# RAVEN_1_0.net
KiCad netlist of a schematic drawn in Altium Designer
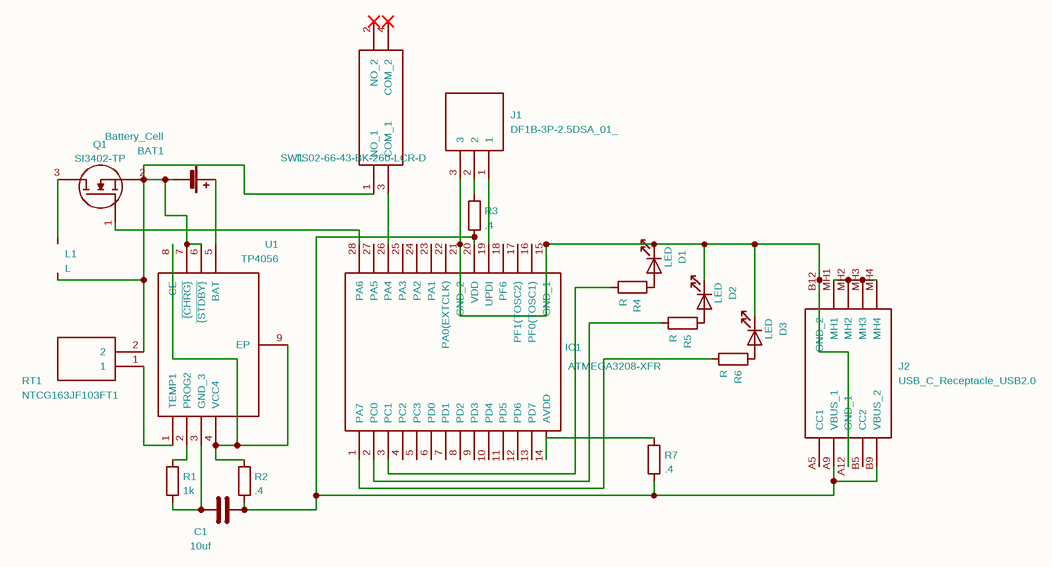
[diagram p0: RAVEN 1.0.SchDoc]

(export (version "E")
  (design (tool "Eeschema 10.0.6"))
  (components
    (comp (ref "BAT1") (value "Battery_Cell") (libsource (lib "Device") (part "Battery_Cell")))
    (comp (ref "C1") (value "10uf") (libsource (lib "Device") (part "C")))
    (comp (ref "D1") (value "LED") (libsource (lib "Device") (part "LED")))
    (comp (ref "D2") (value "LED") (libsource (lib "Device") (part "LED")))
    (comp (ref "D3") (value "LED") (libsource (lib "Device") (part "LED")))
    (comp (ref "IC1")
      (value "ATMEGA3208-XFR")
      (description "8-bit Microcontrollers - MCU 20MHz, 32KB, SSOP28, Ind 125C, Green, T&R")
      (fields (field (name "MOUSER PART NUMBER") "556-ATMEGA3208-XFR"))
      (libsource (lib "SamacSys_Parts_OLD") (part "ATMEGA3208-XFR"))
    )
    (comp (ref "J1")
      (value "DF1B-3P-2.5DSA_01_")
      (description "Headers & Wire Housings 2.5MM V SNG ROW HDR 3P THRU-HOLE GOLD")
      (fields
        (field (name "MANUFACTURER_PART_NUMBER") "DF1B-3P-2.5DSA(01)")
        (field (name "MOUSER PART NUMBER") "798-DF1B-3P-2.5DSA01")
      )
      (libsource (lib "SamacSys_Parts") (part "DF1B-3P-2.5DSA_01_"))
    )
    (comp (ref "J2")
      (value "USB_C_Receptacle_USB2.0")
      (description "USB Connectors USB C Rec GF RA 6P SMT TH Stakes 1.9mm")
      (fields
        (field (name "MANUFACTURER_PART_NUMBER") "USB4125-GF-A-0190")
        (field (name "MOUSER PART NUMBER") "640-USB4125-GF-A-190")
      )
      (libsource (lib "SamacSys_Parts") (part "USB4125-GF-A-0190"))
    )
    (comp (ref "L1") (value "L") (libsource (lib "Device") (part "L")))
    (comp (ref "Q1")
      (value "SI3402-TP")
      (description "MOSFET 30V,4A,N-CHANNEL MOSFET,SOT-23")
      (fields (field (name "MOUSER PART NUMBER") "833-SI3402-TP"))
      (libsource (lib "SamacSys_Parts_OLD") (part "SI3402-TP"))
    )
    (comp (ref "R1") (value "1k") (libsource (lib "") (part "R_1")))
    (comp (ref "R2") (value ".4") (libsource (lib "") (part "R_1")))
    (comp (ref "R3") (value ".4") (libsource (lib "") (part "R_1")))
    (comp (ref "R4") (value "R") (libsource (lib "Device") (part "R")))
    (comp (ref "R5") (value "R") (libsource (lib "Device") (part "R")))
    (comp (ref "R6") (value "R") (libsource (lib "Device") (part "R")))
    (comp (ref "R7") (value ".4") (libsource (lib "") (part "R_1")))
    (comp (ref "RT1")
      (value "NTCG163JF103FT1")
      (description "Chip NTC Thermistors (Sensor), Resistance (at 25?C)=10k?, Resistance Tolerance (at 25?C)=?1%")
      (fields (field (name "MOUSER PART NUMBER") "810-NTCG163JF103FT1"))
      (libsource (lib "SamacSys_Parts_OLD") (part "NTCG163JF103FT1"))
    )
    (comp (ref "SW1")
      (value "TS02-66-43-BK-260-LCR-D")
      (description "Tactile Switches 6 x 6 mm, 4.3 mm Act Height, 260 gf, Black, Long Crimped, Through Hole, SPST,")
      (fields (field (name "MOUSER PART NUMBER") "179-TS026643BK260LCR"))
      (libsource (lib "SamacSys_Parts") (part "TS02-66-43-BK-260-LCR-D"))
    )
    (comp (ref "U1")
      (value "TP4056")
      (description "1A Standalone Linear Li-lon Battery Charger, SOP-8")
      (libsource (lib "SamacSys_Parts_OLD") (part "TP4056"))
    )
  )
  (nets
    (net (code "1") (name "Net-(BAT1-+)") (class "Default")
      (node (ref "BAT1") (pin "1") (pinfunction "+_1") (pintype "passive"))
      (node (ref "U1") (pin "5") (pinfunction "BAT_5") (pintype "passive"))
    )
    (net (code "2") (name "Net-(BAT1--)") (class "Default")
      (node (ref "BAT1") (pin "2") (pinfunction "-_2") (pintype "passive"))
      (node (ref "L1") (pin "2") (pinfunction "2_2") (pintype "passive"))
      (node (ref "Q1") (pin "2") (pinfunction "2_2") (pintype "passive"))
      (node (ref "RT1") (pin "2") (pinfunction "2_2") (pintype "passive"))
      (node (ref "SW1") (pin "1") (pinfunction "NO_1_1") (pintype "passive"))
      (node (ref "U1") (pin "6") (pinfunction "~{{STDBY}}_6") (pintype "passive"))
      (node (ref "U1") (pin "7") (pinfunction "~{{CHRG}}_7") (pintype "passive"))
    )
    (net (code "3") (name "Net-(D1-A)") (class "Default")
      (node (ref "D1") (pin "2") (pinfunction "A_2") (pintype "passive"))
      (node (ref "R4") (pin "1") (pinfunction "1_1") (pintype "passive"))
    )
    (net (code "4") (name "Net-(D1-K)") (class "Default")
      (node (ref "D1") (pin "1") (pinfunction "K_1") (pintype "passive"))
      (node (ref "D2") (pin "1") (pinfunction "K_1") (pintype "passive"))
      (node (ref "D3") (pin "1") (pinfunction "K_1") (pintype "passive"))
      (node (ref "IC1") (pin "15") (pinfunction "GND_1_15") (pintype "passive"))
      (node (ref "IC1") (pin "21") (pinfunction "GND_2_21") (pintype "passive"))
      (node (ref "J1") (pin "3") (pinfunction "3_3") (pintype "passive"))
      (node (ref "J2") (pin "A12") (pinfunction "GND_1_A12") (pintype "passive"))
      (node (ref "J2") (pin "B12") (pinfunction "GND_2_B12") (pintype "passive"))
    )
    (net (code "5") (name "Net-(D2-A)") (class "Default")
      (node (ref "D2") (pin "2") (pinfunction "A_2") (pintype "passive"))
      (node (ref "R5") (pin "1") (pinfunction "1_1") (pintype "passive"))
    )
    (net (code "6") (name "Net-(D3-A)") (class "Default")
      (node (ref "D3") (pin "2") (pinfunction "A_2") (pintype "passive"))
      (node (ref "R6") (pin "1") (pinfunction "1_1") (pintype "passive"))
    )
    (net (code "7") (name "Net-(IC1-AVDD)") (class "Default")
      (node (ref "IC1") (pin "14") (pinfunction "AVDD_14") (pintype "passive"))
      (node (ref "R7") (pin "1") (pinfunction "1_1") (pintype "passive"))
    )
    (net (code "8") (name "Net-(IC1-PA4)") (class "Default")
      (node (ref "IC1") (pin "26") (pinfunction "PA4_26") (pintype "passive"))
      (node (ref "SW1") (pin "3") (pinfunction "COM_1_3") (pintype "passive"))
    )
    (net (code "9") (name "Net-(IC1-PA6)") (class "Default")
      (node (ref "IC1") (pin "28") (pinfunction "PA6_28") (pintype "passive"))
      (node (ref "Q1") (pin "1") (pinfunction "1_1") (pintype "passive"))
    )
    (net (code "10") (name "Net-(IC1-PA7)") (class "Default")
      (node (ref "IC1") (pin "1") (pinfunction "PA7_1") (pintype "passive"))
      (node (ref "R6") (pin "2") (pinfunction "2_2") (pintype "passive"))
    )
    (net (code "11") (name "Net-(IC1-PC0)") (class "Default")
      (node (ref "IC1") (pin "2") (pinfunction "PC0_2") (pintype "passive"))
      (node (ref "R5") (pin "2") (pinfunction "2_2") (pintype "passive"))
    )
    (net (code "12") (name "Net-(IC1-PC1)") (class "Default")
      (node (ref "IC1") (pin "3") (pinfunction "PC1_3") (pintype "passive"))
      (node (ref "R4") (pin "2") (pinfunction "2_2") (pintype "passive"))
    )
    (net (code "13") (name "Net-(IC1-UPDI)") (class "Default")
      (node (ref "IC1") (pin "19") (pinfunction "UPDI_19") (pintype "passive"))
      (node (ref "J1") (pin "1") (pinfunction "1_1") (pintype "passive"))
    )
    (net (code "14") (name "Net-(IC1-VDD)") (class "Default")
      (node (ref "C1") (pin "2") (pinfunction "2_2") (pintype "passive"))
      (node (ref "IC1") (pin "20") (pinfunction "VDD_20") (pintype "passive"))
      (node (ref "J2") (pin "A9") (pinfunction "VBUS_1_A9") (pintype "passive"))
      (node (ref "J2") (pin "B9") (pinfunction "VBUS_2_B9") (pintype "passive"))
      (node (ref "R2") (pin "2") (pinfunction "2_2") (pintype "passive"))
      (node (ref "R3") (pin "2") (pinfunction "2_2") (pintype "passive"))
      (node (ref "R7") (pin "2") (pinfunction "2_2") (pintype "passive"))
    )
    (net (code "15") (name "Net-(J1-Pad2)") (class "Default")
      (node (ref "J1") (pin "2") (pinfunction "2_2") (pintype "passive"))
      (node (ref "R3") (pin "1") (pinfunction "1_1") (pintype "passive"))
    )
    (net (code "16") (name "Net-(J2-PadMH1)") (class "Default")
      (node (ref "J2") (pin "MH1") (pinfunction "MH1_MH1") (pintype "passive"))
      (node (ref "J2") (pin "MH2") (pinfunction "MH2_MH2") (pintype "passive"))
      (node (ref "J2") (pin "MH3") (pinfunction "MH3_MH3") (pintype "passive"))
      (node (ref "J2") (pin "MH4") (pinfunction "MH4_MH4") (pintype "passive"))
    )
    (net (code "17") (name "Net-(L1-Pad1)") (class "Default")
      (node (ref "L1") (pin "1") (pinfunction "1_1") (pintype "passive"))
      (node (ref "Q1") (pin "3") (pinfunction "3_3") (pintype "passive"))
    )
    (net (code "18") (name "Net-(U1-CE)") (class "Default")
      (node (ref "R2") (pin "1") (pinfunction "1_1") (pintype "passive"))
      (node (ref "U1") (pin "4") (pinfunction "VCC4_4") (pintype "passive"))
      (node (ref "U1") (pin "8") (pinfunction "CE_8") (pintype "passive"))
      (node (ref "U1") (pin "9") (pinfunction "EP_9") (pintype "passive"))
    )
    (net (code "19") (name "Net-(U1-GND_3)") (class "Default")
      (node (ref "C1") (pin "1") (pinfunction "1_1") (pintype "passive"))
      (node (ref "R1") (pin "2") (pinfunction "2_2") (pintype "passive"))
      (node (ref "U1") (pin "3") (pinfunction "GND_3_3") (pintype "passive"))
    )
    (net (code "20") (name "Net-(U1-PROG2)") (class "Default")
      (node (ref "R1") (pin "1") (pinfunction "1_1") (pintype "passive"))
      (node (ref "U1") (pin "2") (pinfunction "PROG2_2") (pintype "passive"))
    )
    (net (code "21") (name "Net-(U1-TEMP1)") (class "Default")
      (node (ref "RT1") (pin "1") (pinfunction "1_1") (pintype "passive"))
      (node (ref "U1") (pin "1") (pinfunction "TEMP1_1") (pintype "passive"))
    )
    (net (code "22") (name "unconnected-(IC1-PA0(EXTCLK)-Pad22)") (class "Default")
      (node (ref "IC1") (pin "22") (pinfunction "PA0(EXTCLK)_22") (pintype "passive"))
    )
    (net (code "23") (name "unconnected-(IC1-PA1-Pad23)") (class "Default")
      (node (ref "IC1") (pin "23") (pinfunction "PA1_23") (pintype "passive"))
    )
    (net (code "24") (name "unconnected-(IC1-PA2-Pad24)") (class "Default")
      (node (ref "IC1") (pin "24") (pinfunction "PA2_24") (pintype "passive"))
    )
    (net (code "25") (name "unconnected-(IC1-PA3-Pad25)") (class "Default")
      (node (ref "IC1") (pin "25") (pinfunction "PA3_25") (pintype "passive"))
    )
    (net (code "26") (name "unconnected-(IC1-PA5-Pad27)") (class "Default")
      (node (ref "IC1") (pin "27") (pinfunction "PA5_27") (pintype "passive"))
    )
    (net (code "27") (name "unconnected-(IC1-PC2-Pad4)") (class "Default")
      (node (ref "IC1") (pin "4") (pinfunction "PC2_4") (pintype "passive"))
    )
    (net (code "28") (name "unconnected-(IC1-PC3-Pad5)") (class "Default")
      (node (ref "IC1") (pin "5") (pinfunction "PC3_5") (pintype "passive"))
    )
    (net (code "29") (name "unconnected-(IC1-PD0-Pad6)") (class "Default")
      (node (ref "IC1") (pin "6") (pinfunction "PD0_6") (pintype "passive"))
    )
    (net (code "30") (name "unconnected-(IC1-PD1-Pad7)") (class "Default")
      (node (ref "IC1") (pin "7") (pinfunction "PD1_7") (pintype "passive"))
    )
    (net (code "31") (name "unconnected-(IC1-PD2-Pad8)") (class "Default")
      (node (ref "IC1") (pin "8") (pinfunction "PD2_8") (pintype "passive"))
    )
    (net (code "32") (name "unconnected-(IC1-PD3-Pad9)") (class "Default")
      (node (ref "IC1") (pin "9") (pinfunction "PD3_9") (pintype "passive"))
    )
    (net (code "33") (name "unconnected-(IC1-PD4-Pad10)") (class "Default")
      (node (ref "IC1") (pin "10") (pinfunction "PD4_10") (pintype "passive"))
    )
    (net (code "34") (name "unconnected-(IC1-PD5-Pad11)") (class "Default")
      (node (ref "IC1") (pin "11") (pinfunction "PD5_11") (pintype "passive"))
    )
    (net (code "35") (name "unconnected-(IC1-PD6-Pad12)") (class "Default")
      (node (ref "IC1") (pin "12") (pinfunction "PD6_12") (pintype "passive"))
    )
    (net (code "36") (name "unconnected-(IC1-PD7-Pad13)") (class "Default")
      (node (ref "IC1") (pin "13") (pinfunction "PD7_13") (pintype "passive"))
    )
    (net (code "37") (name "unconnected-(IC1-PF0(TOSC1)-Pad16)") (class "Default")
      (node (ref "IC1") (pin "16") (pinfunction "PF0(TOSC1)_16") (pintype "passive"))
    )
    (net (code "38") (name "unconnected-(IC1-PF1(TOSC2)-Pad17)") (class "Default")
      (node (ref "IC1") (pin "17") (pinfunction "PF1(TOSC2)_17") (pintype "passive"))
    )
    (net (code "39") (name "unconnected-(IC1-PF6-Pad18)") (class "Default")
      (node (ref "IC1") (pin "18") (pinfunction "PF6_18") (pintype "passive"))
    )
    (net (code "40") (name "unconnected-(J2-CC1-PadA5)") (class "Default")
      (node (ref "J2") (pin "A5") (pinfunction "CC1_A5") (pintype "passive"))
    )
    (net (code "41") (name "unconnected-(J2-CC2-PadB5)") (class "Default")
      (node (ref "J2") (pin "B5") (pinfunction "CC2_B5") (pintype "passive"))
    )
    (net (code "42") (name "unconnected-(SW1-COM_2-Pad4)") (class "Default")
      (node (ref "SW1") (pin "4") (pinfunction "COM_2_4") (pintype "passive+no_connect"))
    )
    (net (code "43") (name "unconnected-(SW1-NO_2-Pad2)") (class "Default")
      (node (ref "SW1") (pin "2") (pinfunction "NO_2_2") (pintype "passive+no_connect"))
    )
  )
)
